# Analog_Supply_and_TIA.net
KiCad netlist of a schematic drawn in Altium Designer
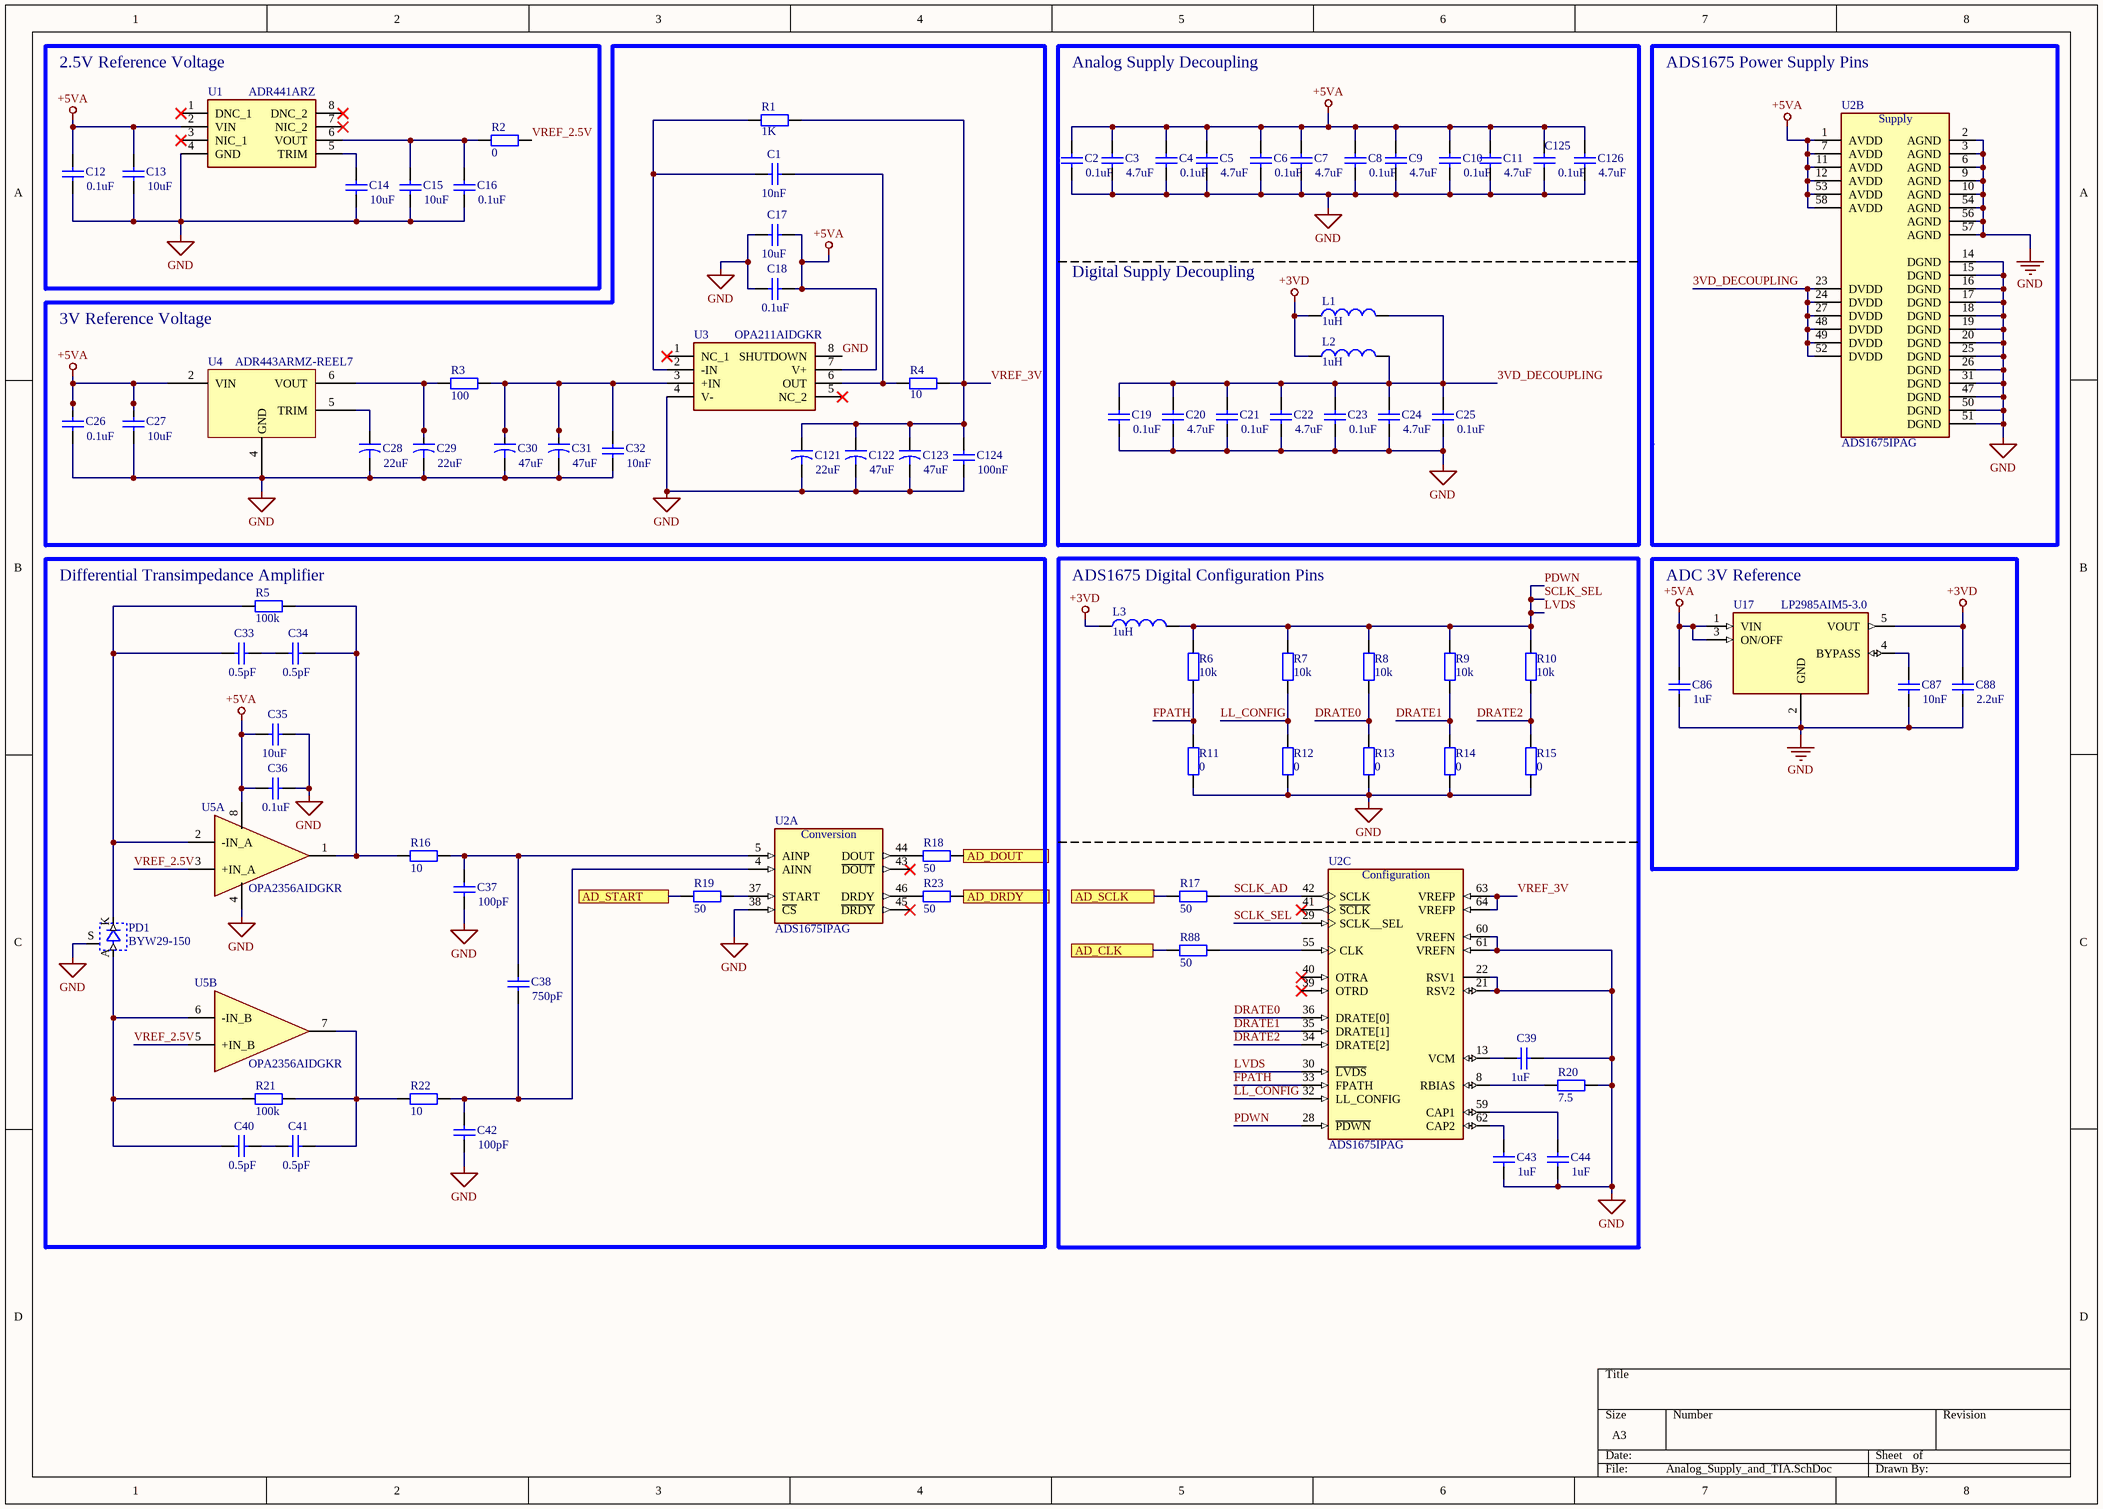
[diagram p0: Analog_Supply_and_TIA.SchDoc]

(export (version "E")
  (design (tool "Eeschema 10.0.6"))
  (components
    (comp (ref "C1")
      (value "10nF")
      (footprint "CC_0805")
      (description "Capacitor")
      (fields (field (name "Comment") "Cap") (field (name "PUBLISHER") "Altium Limited"))
      (libsource (lib "Miscellaneous Devices") (part "Cap"))
    )
    (comp (ref "C2")
      (value "0.1uF")
      (footprint "CC_0805")
      (description "Capacitor")
      (fields (field (name "Comment") "Cap") (field (name "PUBLISHER") "Altium Limited"))
      (libsource (lib "Miscellaneous Devices") (part "Cap"))
    )
    (comp (ref "C3")
      (value "4.7uF")
      (footprint "CC_0805")
      (description "Capacitor")
      (fields (field (name "Comment") "Cap") (field (name "PUBLISHER") "Altium Limited"))
      (libsource (lib "Miscellaneous Devices") (part "Cap"))
    )
    (comp (ref "C4")
      (value "0.1uF")
      (footprint "CC_0805")
      (description "Capacitor")
      (fields (field (name "Comment") "Cap") (field (name "PUBLISHER") "Altium Limited"))
      (libsource (lib "Miscellaneous Devices") (part "Cap"))
    )
    (comp (ref "C5")
      (value "4.7uF")
      (footprint "CC_0805")
      (description "Capacitor")
      (fields (field (name "Comment") "Cap") (field (name "PUBLISHER") "Altium Limited"))
      (libsource (lib "Miscellaneous Devices") (part "Cap"))
    )
    (comp (ref "C6")
      (value "0.1uF")
      (footprint "CC_0805")
      (description "Capacitor")
      (fields (field (name "Comment") "Cap") (field (name "PUBLISHER") "Altium Limited"))
      (libsource (lib "Miscellaneous Devices") (part "Cap"))
    )
    (comp (ref "C7")
      (value "4.7uF")
      (footprint "CC_0805")
      (description "Capacitor")
      (fields (field (name "Comment") "Cap") (field (name "PUBLISHER") "Altium Limited"))
      (libsource (lib "Miscellaneous Devices") (part "Cap"))
    )
    (comp (ref "C8")
      (value "0.1uF")
      (footprint "CC_0805")
      (description "Capacitor")
      (fields (field (name "Comment") "Cap") (field (name "PUBLISHER") "Altium Limited"))
      (libsource (lib "Miscellaneous Devices") (part "Cap"))
    )
    (comp (ref "C9")
      (value "4.7uF")
      (footprint "CC_0805")
      (description "Capacitor")
      (fields (field (name "Comment") "Cap") (field (name "PUBLISHER") "Altium Limited"))
      (libsource (lib "Miscellaneous Devices") (part "Cap"))
    )
    (comp (ref "C10")
      (value "0.1uF")
      (footprint "CC_0805")
      (description "Capacitor")
      (fields (field (name "Comment") "Cap") (field (name "PUBLISHER") "Altium Limited"))
      (libsource (lib "Miscellaneous Devices") (part "Cap"))
    )
    (comp (ref "C11")
      (value "4.7uF")
      (footprint "CC_0805")
      (description "Capacitor")
      (fields (field (name "Comment") "Cap") (field (name "PUBLISHER") "Altium Limited"))
      (libsource (lib "Miscellaneous Devices") (part "Cap"))
    )
    (comp (ref "C12")
      (value "0.1uF")
      (footprint "CC_0805")
      (description "Capacitor")
      (fields (field (name "Comment") "Cap") (field (name "PUBLISHER") "Altium Limited"))
      (libsource (lib "Miscellaneous Devices") (part "Cap"))
    )
    (comp (ref "C13")
      (value "10uF")
      (footprint "CC_0805")
      (description "Capacitor")
      (fields (field (name "Comment") "Cap") (field (name "PUBLISHER") "Altium Limited"))
      (libsource (lib "Miscellaneous Devices") (part "Cap"))
    )
    (comp (ref "C14")
      (value "10uF")
      (footprint "CC_0805")
      (description "Capacitor")
      (fields (field (name "Comment") "Cap") (field (name "PUBLISHER") "Altium Limited"))
      (libsource (lib "Miscellaneous Devices") (part "Cap"))
    )
    (comp (ref "C15")
      (value "10uF")
      (footprint "CC_0805")
      (description "Capacitor")
      (fields (field (name "Comment") "Cap") (field (name "PUBLISHER") "Altium Limited"))
      (libsource (lib "Miscellaneous Devices") (part "Cap"))
    )
    (comp (ref "C16")
      (value "0.1uF")
      (footprint "CC_0805")
      (description "Capacitor")
      (fields (field (name "Comment") "Cap") (field (name "PUBLISHER") "Altium Limited"))
      (libsource (lib "Miscellaneous Devices") (part "Cap"))
    )
    (comp (ref "C17")
      (value "10uF")
      (footprint "CC_0805")
      (description "Capacitor")
      (fields (field (name "Comment") "Cap") (field (name "PUBLISHER") "Altium Limited"))
      (libsource (lib "Miscellaneous Devices") (part "Cap"))
    )
    (comp (ref "C18")
      (value "0.1uF")
      (footprint "CC_0805")
      (description "Capacitor")
      (fields (field (name "Comment") "Cap") (field (name "PUBLISHER") "Altium Limited"))
      (libsource (lib "Miscellaneous Devices") (part "Cap"))
    )
    (comp (ref "C19")
      (value "0.1uF")
      (footprint "CC_0805")
      (description "Capacitor")
      (fields (field (name "Comment") "Cap") (field (name "PUBLISHER") "Altium Limited"))
      (libsource (lib "Miscellaneous Devices") (part "Cap"))
    )
    (comp (ref "C20")
      (value "4.7uF")
      (footprint "CC_0805")
      (description "Capacitor")
      (fields (field (name "Comment") "Cap") (field (name "PUBLISHER") "Altium Limited"))
      (libsource (lib "Miscellaneous Devices") (part "Cap"))
    )
    (comp (ref "C21")
      (value "0.1uF")
      (footprint "CC_0805")
      (description "Capacitor")
      (fields (field (name "Comment") "Cap") (field (name "PUBLISHER") "Altium Limited"))
      (libsource (lib "Miscellaneous Devices") (part "Cap"))
    )
    (comp (ref "C22")
      (value "4.7uF")
      (footprint "CC_0805")
      (description "Capacitor")
      (fields (field (name "Comment") "Cap") (field (name "PUBLISHER") "Altium Limited"))
      (libsource (lib "Miscellaneous Devices") (part "Cap"))
    )
    (comp (ref "C23")
      (value "0.1uF")
      (footprint "CC_0805")
      (description "Capacitor")
      (fields (field (name "Comment") "Cap") (field (name "PUBLISHER") "Altium Limited"))
      (libsource (lib "Miscellaneous Devices") (part "Cap"))
    )
    (comp (ref "C24")
      (value "4.7uF")
      (footprint "CC_0805")
      (description "Capacitor")
      (fields (field (name "Comment") "Cap") (field (name "PUBLISHER") "Altium Limited"))
      (libsource (lib "Miscellaneous Devices") (part "Cap"))
    )
    (comp (ref "C25")
      (value "0.1uF")
      (footprint "CC_0805")
      (description "Capacitor")
      (fields (field (name "Comment") "Cap") (field (name "PUBLISHER") "Altium Limited"))
      (libsource (lib "Miscellaneous Devices") (part "Cap"))
    )
    (comp (ref "C26")
      (value "0.1uF")
      (footprint "CC_0805")
      (description "Capacitor")
      (fields (field (name "Comment") "Cap") (field (name "PUBLISHER") "Altium Limited"))
      (libsource (lib "Miscellaneous Devices") (part "Cap"))
    )
    (comp (ref "C27")
      (value "10uF")
      (footprint "CC_0805")
      (description "Capacitor")
      (fields (field (name "Comment") "Cap") (field (name "PUBLISHER") "Altium Limited"))
      (libsource (lib "Miscellaneous Devices") (part "Cap"))
    )
    (comp (ref "C28")
      (value "22uF")
      (footprint "CC_0805")
      (description "Capacitor")
      (fields (field (name "Comment") "Cap2") (field (name "PUBLISHER") "Altium Limited"))
      (libsource (lib "Miscellaneous Devices") (part "Cap2"))
    )
    (comp (ref "C29")
      (value "22uF")
      (footprint "CC_0805")
      (description "Capacitor")
      (fields (field (name "Comment") "Cap2") (field (name "PUBLISHER") "Altium Limited"))
      (libsource (lib "Miscellaneous Devices") (part "Cap2"))
    )
    (comp (ref "C30")
      (value "47uF")
      (footprint "CC_0805")
      (description "Capacitor")
      (fields (field (name "Comment") "Cap2") (field (name "PUBLISHER") "Altium Limited"))
      (libsource (lib "Miscellaneous Devices") (part "Cap2"))
    )
    (comp (ref "C31")
      (value "47uF")
      (footprint "CC_0805")
      (description "Capacitor")
      (fields (field (name "Comment") "Cap2") (field (name "PUBLISHER") "Altium Limited"))
      (libsource (lib "Miscellaneous Devices") (part "Cap2"))
    )
    (comp (ref "C32")
      (value "10nF")
      (footprint "CC_0805")
      (description "Capacitor")
      (fields (field (name "Comment") "Cap") (field (name "PUBLISHER") "Altium Limited"))
      (libsource (lib "Miscellaneous Devices") (part "Cap"))
    )
    (comp (ref "C33")
      (value "0.5pF")
      (footprint "CC_0805")
      (description "Capacitor")
      (fields (field (name "Comment") "Cap") (field (name "PUBLISHER") "Altium Limited"))
      (libsource (lib "Miscellaneous Devices") (part "Cap"))
    )
    (comp (ref "C34")
      (value "0.5pF")
      (footprint "CC_0805")
      (description "Capacitor")
      (fields (field (name "Comment") "Cap") (field (name "PUBLISHER") "Altium Limited"))
      (libsource (lib "Miscellaneous Devices") (part "Cap"))
    )
    (comp (ref "C35")
      (value "10uF")
      (footprint "CC_0805")
      (description "Capacitor")
      (fields (field (name "Comment") "Cap") (field (name "PUBLISHER") "Altium Limited"))
      (libsource (lib "Miscellaneous Devices") (part "Cap"))
    )
    (comp (ref "C36")
      (value "0.1uF")
      (footprint "CC_0805")
      (description "Capacitor")
      (fields (field (name "Comment") "Cap") (field (name "PUBLISHER") "Altium Limited"))
      (libsource (lib "Miscellaneous Devices") (part "Cap"))
    )
    (comp (ref "C37")
      (value "100pF")
      (footprint "CC_0805")
      (description "Capacitor")
      (fields (field (name "Comment") "Cap") (field (name "PUBLISHER") "Altium Limited"))
      (libsource (lib "Miscellaneous Devices") (part "Cap"))
    )
    (comp (ref "C38")
      (value "750pF")
      (footprint "CC_0805")
      (description "Capacitor")
      (fields (field (name "Comment") "Cap") (field (name "PUBLISHER") "Altium Limited"))
      (libsource (lib "Miscellaneous Devices") (part "Cap"))
    )
    (comp (ref "C39")
      (value "1uF")
      (footprint "CC_0805")
      (description "Capacitor")
      (fields (field (name "Comment") "Cap") (field (name "PUBLISHER") "Altium Limited"))
      (libsource (lib "Miscellaneous Devices") (part "Cap"))
    )
    (comp (ref "C40")
      (value "0.5pF")
      (footprint "CC_0805")
      (description "Capacitor")
      (fields (field (name "Comment") "Cap") (field (name "PUBLISHER") "Altium Limited"))
      (libsource (lib "Miscellaneous Devices") (part "Cap"))
    )
    (comp (ref "C41")
      (value "0.5pF")
      (footprint "CC_0805")
      (description "Capacitor")
      (fields (field (name "Comment") "Cap") (field (name "PUBLISHER") "Altium Limited"))
      (libsource (lib "Miscellaneous Devices") (part "Cap"))
    )
    (comp (ref "C42")
      (value "100pF")
      (footprint "CC_0805")
      (description "Capacitor")
      (fields (field (name "Comment") "Cap") (field (name "PUBLISHER") "Altium Limited"))
      (libsource (lib "Miscellaneous Devices") (part "Cap"))
    )
    (comp (ref "C43")
      (value "1uF")
      (footprint "CC_0805")
      (description "Capacitor")
      (fields (field (name "Comment") "Cap") (field (name "PUBLISHER") "Altium Limited"))
      (libsource (lib "Miscellaneous Devices") (part "Cap"))
    )
    (comp (ref "C44")
      (value "1uF")
      (footprint "CC_0805")
      (description "Capacitor")
      (fields (field (name "Comment") "Cap") (field (name "PUBLISHER") "Altium Limited"))
      (libsource (lib "Miscellaneous Devices") (part "Cap"))
    )
    (comp (ref "C86")
      (value "1uF")
      (footprint "CC_0805")
      (description "Capacitor")
      (fields (field (name "Comment") "Cap") (field (name "PUBLISHER") "Altium Limited"))
      (libsource (lib "Miscellaneous Devices") (part "Cap"))
    )
    (comp (ref "C87")
      (value "10nF")
      (footprint "CC_0805")
      (description "Capacitor")
      (fields (field (name "Comment") "Cap") (field (name "PUBLISHER") "Altium Limited"))
      (libsource (lib "Miscellaneous Devices") (part "Cap"))
    )
    (comp (ref "C88")
      (value "2.2uF")
      (footprint "CC_0805")
      (description "Capacitor")
      (fields (field (name "Comment") "Cap") (field (name "PUBLISHER") "Altium Limited"))
      (libsource (lib "Miscellaneous Devices") (part "Cap"))
    )
    (comp (ref "C121")
      (value "22uF")
      (footprint "CC_0805")
      (description "Capacitor")
      (fields (field (name "Comment") "Cap2") (field (name "PUBLISHER") "Altium Limited"))
      (libsource (lib "Miscellaneous Devices") (part "Cap2"))
    )
    (comp (ref "C122")
      (value "47uF")
      (footprint "CC_0805")
      (description "Capacitor")
      (fields (field (name "Comment") "Cap2") (field (name "PUBLISHER") "Altium Limited"))
      (libsource (lib "Miscellaneous Devices") (part "Cap2"))
    )
    (comp (ref "C123")
      (value "47uF")
      (footprint "CC_0805")
      (description "Capacitor")
      (fields (field (name "Comment") "Cap2") (field (name "PUBLISHER") "Altium Limited"))
      (libsource (lib "Miscellaneous Devices") (part "Cap2"))
    )
    (comp (ref "C124")
      (value "100nF")
      (footprint "CC_0805")
      (description "Capacitor")
      (fields (field (name "Comment") "Cap") (field (name "PUBLISHER") "Altium Limited"))
      (libsource (lib "Miscellaneous Devices") (part "Cap"))
    )
    (comp (ref "C125")
      (value "0.1uF")
      (footprint "CC_0805")
      (description "Capacitor")
      (fields (field (name "Comment") "Cap") (field (name "PUBLISHER") "Altium Limited"))
      (libsource (lib "Miscellaneous Devices") (part "Cap"))
    )
    (comp (ref "C126")
      (value "4.7uF")
      (footprint "CC_0805")
      (description "Capacitor")
      (fields (field (name "Comment") "Cap") (field (name "PUBLISHER") "Altium Limited"))
      (libsource (lib "Miscellaneous Devices") (part "Cap"))
    )
    (comp (ref "L1")
      (value "1uH")
      (footprint "WE-PMI_0805_H0.5")
      (description "Inductor")
      (fields (field (name "PUBLISHER") "Altium Limited"))
      (libsource (lib "Miscellaneous Devices") (part "Inductor"))
    )
    (comp (ref "L2")
      (value "1uH")
      (footprint "WE-PMI_0805_H0.5")
      (description "Inductor")
      (fields (field (name "PUBLISHER") "Altium Limited"))
      (libsource (lib "Miscellaneous Devices") (part "Inductor"))
    )
    (comp (ref "L3")
      (value "1uH")
      (footprint "WE-PMI_0805_H0.5")
      (description "Inductor")
      (fields (field (name "PUBLISHER") "Altium Limited"))
      (libsource (lib "Miscellaneous Devices") (part "Inductor"))
    )
    (comp (ref "PD1")
      (value "BYW29-150")
      (footprint "BYW29-150")
      (libsource (lib "Lib_Schematic_IFOG_Interrogator") (part "BYW29-150"))
    )
    (comp (ref "R1")
      (value "1K")
      (footprint "RR_1220")
      (description "Resistor")
      (fields (field (name "Comment") "Res2") (field (name "PUBLISHER") "Altium Limited"))
      (libsource (lib "") (part "Res2_1"))
    )
    (comp (ref "R2")
      (value "0")
      (footprint "RR_1220")
      (description "Resistor")
      (fields (field (name "Comment") "Res2") (field (name "PUBLISHER") "Altium Limited"))
      (libsource (lib "") (part "Res2_2"))
    )
    (comp (ref "R3")
      (value "100")
      (footprint "RR_1220")
      (description "Resistor")
      (fields (field (name "Comment") "Res2") (field (name "PUBLISHER") "Altium Limited"))
      (libsource (lib "") (part "Res2_2"))
    )
    (comp (ref "R4")
      (value "10")
      (footprint "RR_1220")
      (description "Resistor")
      (fields (field (name "Comment") "Res2") (field (name "PUBLISHER") "Altium Limited"))
      (libsource (lib "") (part "Res2_1"))
    )
    (comp (ref "R5")
      (value "100k")
      (footprint "RR_1220")
      (description "Resistor")
      (fields (field (name "Comment") "Res2") (field (name "PUBLISHER") "Altium Limited"))
      (libsource (lib "") (part "Res2_2"))
    )
    (comp (ref "R6")
      (value "10k")
      (footprint "RR_1220")
      (description "Resistor")
      (fields (field (name "Comment") "Res2") (field (name "PUBLISHER") "Altium Limited"))
      (libsource (lib "Miscellaneous Devices") (part "Res2"))
    )
    (comp (ref "R7")
      (value "10k")
      (footprint "RR_1220")
      (description "Resistor")
      (fields (field (name "Comment") "Res2") (field (name "PUBLISHER") "Altium Limited"))
      (libsource (lib "Miscellaneous Devices") (part "Res2"))
    )
    (comp (ref "R8")
      (value "10k")
      (footprint "RR_1220")
      (description "Resistor")
      (fields (field (name "Comment") "Res2") (field (name "PUBLISHER") "Altium Limited"))
      (libsource (lib "Miscellaneous Devices") (part "Res2"))
    )
    (comp (ref "R9")
      (value "10k")
      (footprint "RR_1220")
      (description "Resistor")
      (fields (field (name "Comment") "Res2") (field (name "PUBLISHER") "Altium Limited"))
      (libsource (lib "Miscellaneous Devices") (part "Res2"))
    )
    (comp (ref "R10")
      (value "10k")
      (footprint "RR_1220")
      (description "Resistor")
      (fields (field (name "Comment") "Res2") (field (name "PUBLISHER") "Altium Limited"))
      (libsource (lib "Miscellaneous Devices") (part "Res2"))
    )
    (comp (ref "R11")
      (value "0")
      (footprint "RR_1220")
      (description "Resistor")
      (fields (field (name "Comment") "Res2") (field (name "PUBLISHER") "Altium Limited"))
      (libsource (lib "Miscellaneous Devices") (part "Res2"))
    )
    (comp (ref "R12")
      (value "0")
      (footprint "RR_1220")
      (description "Resistor")
      (fields (field (name "Comment") "Res2") (field (name "PUBLISHER") "Altium Limited"))
      (libsource (lib "Miscellaneous Devices") (part "Res2"))
    )
    (comp (ref "R13")
      (value "0")
      (footprint "RR_1220")
      (description "Resistor")
      (fields (field (name "Comment") "Res2") (field (name "PUBLISHER") "Altium Limited"))
      (libsource (lib "Miscellaneous Devices") (part "Res2"))
    )
    (comp (ref "R14")
      (value "0")
      (footprint "RR_1220")
      (description "Resistor")
      (fields (field (name "Comment") "Res2") (field (name "PUBLISHER") "Altium Limited"))
      (libsource (lib "Miscellaneous Devices") (part "Res2"))
    )
    (comp (ref "R15")
      (value "0")
      (footprint "RR_1220")
      (description "Resistor")
      (fields (field (name "Comment") "Res2") (field (name "PUBLISHER") "Altium Limited"))
      (libsource (lib "Miscellaneous Devices") (part "Res2"))
    )
    (comp (ref "R16")
      (value "10")
      (footprint "RR_1220")
      (description "Resistor")
      (fields (field (name "Comment") "Res2") (field (name "PUBLISHER") "Altium Limited"))
      (libsource (lib "") (part "Res2_2"))
    )
    (comp (ref "R17")
      (value "50")
      (footprint "RR_1220")
      (description "Resistor")
      (fields (field (name "Comment") "Res2") (field (name "PUBLISHER") "Altium Limited"))
      (libsource (lib "") (part "Res2_2"))
    )
    (comp (ref "R18")
      (value "50")
      (footprint "RR_1220")
      (description "Resistor")
      (fields (field (name "Comment") "Res2") (field (name "PUBLISHER") "Altium Limited"))
      (libsource (lib "") (part "Res2_2"))
    )
    (comp (ref "R19")
      (value "50")
      (footprint "RR_1220")
      (description "Resistor")
      (fields (field (name "Comment") "Res2") (field (name "PUBLISHER") "Altium Limited"))
      (libsource (lib "") (part "Res2_2"))
    )
    (comp (ref "R20")
      (value "7.5")
      (footprint "RR_1220")
      (description "Resistor")
      (fields (field (name "Comment") "Res2") (field (name "PUBLISHER") "Altium Limited"))
      (libsource (lib "") (part "Res2_2"))
    )
    (comp (ref "R21")
      (value "100k")
      (footprint "RR_1220")
      (description "Resistor")
      (fields (field (name "Comment") "Res2") (field (name "PUBLISHER") "Altium Limited"))
      (libsource (lib "") (part "Res2_2"))
    )
    (comp (ref "R22")
      (value "10")
      (footprint "RR_1220")
      (description "Resistor")
      (fields (field (name "Comment") "Res2") (field (name "PUBLISHER") "Altium Limited"))
      (libsource (lib "") (part "Res2_2"))
    )
    (comp (ref "R23")
      (value "50")
      (footprint "RR_1220")
      (description "Resistor")
      (fields (field (name "Comment") "Res2") (field (name "PUBLISHER") "Altium Limited"))
      (libsource (lib "") (part "Res2_2"))
    )
    (comp (ref "R88")
      (value "50")
      (footprint "RR_1220")
      (description "Resistor")
      (fields (field (name "Comment") "Res2") (field (name "PUBLISHER") "Altium Limited"))
      (libsource (lib "") (part "Res2_2"))
    )
    (comp (ref "U1")
      (value "ADR441ARZ")
      (footprint "ADR441ARZ")
      (description "Series Voltage Reference IC Fixed 2.5V V +/-0.12% 10 mA 8-SOIC")
      (fields (field (name "MOUSER PART NUMBER") "584-ADR441ARZ"))
      (libsource (lib "Lib_Schematic_Gyro_Single_Axis") (part "ADR441ARZ"))
    )
    (comp (ref "U2")
      (value "ADS1675IPAG")
      (footprint "ADS1675IPAG")
      (description "4MSPS, 24-Bit Analog-to-Digital Converter")
      (fields (field (name "MF") "Texas Instruments"))
      (libsource (lib "Lib_Schematic_IFOG_Interrogator") (part "ADS1675IPAG"))
    )
    (comp (ref "U3")
      (value "OPA211AIDGKR")
      (footprint "OPA211AIDGKR")
      (description "Precision Amplifiers 1.1nV/rtHz Noise Lo Pwr Prec Op Amp")
      (fields (field (name "MOUSER PART NUMBER") "595-OPA211AIDGKR"))
      (libsource (lib "Lib_Schematic_Gyro_Single_Axis") (part "OPA211AIDGKR"))
    )
    (comp (ref "U4")
      (value "ADR443ARMZ-REEL7")
      (footprint "ADR443ARMZ-REEL7 - duplicate")
      (libsource (lib "Lib_Schematic_Gyro_Single_Axis") (part "ADR443ARMZ-REEL7"))
    )
    (comp (ref "U5")
      (value "OPA2356AIDGKR")
      (footprint "OPA2356AIDGKR")
      (description "High Speed Operational Amplifiers 2.5V 200MHz GBW CMOS Dual Op Amp")
      (fields (field (name "MOUSER PART NUMBER") "595-OPA2356AIDGKR"))
      (libsource (lib "Lib_Schematic_Gyro_Single_Axis") (part "OPA2356AIDGKR"))
    )
    (comp (ref "U17")
      (value "LP2985AIM5-3.0")
      (footprint "LP2985AIM5-3.0")
      (description "150-mA, 16-V, low-dropout voltage regulator with enable")
      (fields (field (name "MF") "Texas Instruments") (field (name "MP") "LP2985AIM5-3.0/NOPB"))
      (libsource (lib "Lib_Schematic_Gyro_Single_Axis") (part "LP2985AIM5-3.0"))
    )
  )
  (nets
    (net (code "1") (name "+3VD") (class "Default")
      (node (ref "C88") (pin "1") (pinfunction "1_1") (pintype "passive"))
      (node (ref "L1") (pin "1") (pinfunction "1_1") (pintype "passive"))
      (node (ref "L2") (pin "1") (pinfunction "1_1") (pintype "passive"))
      (node (ref "L3") (pin "1") (pinfunction "1_1") (pintype "passive"))
      (node (ref "U17") (pin "5") (pinfunction "VOUT_5") (pintype "output"))
    )
    (net (code "2") (name "+5VA") (class "Default")
      (node (ref "C10") (pin "2") (pinfunction "2_2") (pintype "passive"))
      (node (ref "C11") (pin "2") (pinfunction "2_2") (pintype "passive"))
      (node (ref "C12") (pin "2") (pinfunction "2_2") (pintype "passive"))
      (node (ref "C125") (pin "2") (pinfunction "2_2") (pintype "passive"))
      (node (ref "C126") (pin "2") (pinfunction "2_2") (pintype "passive"))
      (node (ref "C13") (pin "2") (pinfunction "2_2") (pintype "passive"))
      (node (ref "C17") (pin "1") (pinfunction "1_1") (pintype "passive"))
      (node (ref "C18") (pin "1") (pinfunction "1_1") (pintype "passive"))
      (node (ref "C2") (pin "2") (pinfunction "2_2") (pintype "passive"))
      (node (ref "C26") (pin "2") (pinfunction "2_2") (pintype "passive"))
      (node (ref "C27") (pin "2") (pinfunction "2_2") (pintype "passive"))
      (node (ref "C3") (pin "2") (pinfunction "2_2") (pintype "passive"))
      (node (ref "C35") (pin "2") (pinfunction "2_2") (pintype "passive"))
      (node (ref "C36") (pin "2") (pinfunction "2_2") (pintype "passive"))
      (node (ref "C4") (pin "2") (pinfunction "2_2") (pintype "passive"))
      (node (ref "C5") (pin "2") (pinfunction "2_2") (pintype "passive"))
      (node (ref "C6") (pin "2") (pinfunction "2_2") (pintype "passive"))
      (node (ref "C7") (pin "2") (pinfunction "2_2") (pintype "passive"))
      (node (ref "C8") (pin "2") (pinfunction "2_2") (pintype "passive"))
      (node (ref "C86") (pin "1") (pinfunction "1_1") (pintype "passive"))
      (node (ref "C9") (pin "2") (pinfunction "2_2") (pintype "passive"))
      (node (ref "U1") (pin "2") (pinfunction "VIN_2") (pintype "passive"))
      (node (ref "U17") (pin "1") (pinfunction "VIN_1") (pintype "input"))
      (node (ref "U17") (pin "3") (pinfunction "ON/OFF_3") (pintype "input"))
      (node (ref "U2") (pin "1") (pinfunction "AVDD_1") (pintype "power_in"))
      (node (ref "U2") (pin "11") (pinfunction "AVDD_11") (pintype "power_in"))
      (node (ref "U2") (pin "12") (pinfunction "AVDD_12") (pintype "power_in"))
      (node (ref "U2") (pin "53") (pinfunction "AVDD_53") (pintype "power_in"))
      (node (ref "U2") (pin "58") (pinfunction "AVDD_58") (pintype "power_in"))
      (node (ref "U2") (pin "7") (pinfunction "AVDD_7") (pintype "power_in"))
      (node (ref "U3") (pin "7") (pinfunction "V+_7") (pintype "passive"))
      (node (ref "U4") (pin "2") (pinfunction "VIN_2") (pintype "passive"))
      (node (ref "U5") (pin "8") (pinfunction "V+_8") (pintype "passive"))
    )
    (net (code "3") (name "/3VD_DECOUPLING") (class "Default")
      (node (ref "C19") (pin "2") (pinfunction "2_2") (pintype "passive"))
      (node (ref "C20") (pin "2") (pinfunction "2_2") (pintype "passive"))
      (node (ref "C21") (pin "2") (pinfunction "2_2") (pintype "passive"))
      (node (ref "C22") (pin "2") (pinfunction "2_2") (pintype "passive"))
      (node (ref "C23") (pin "2") (pinfunction "2_2") (pintype "passive"))
      (node (ref "C24") (pin "2") (pinfunction "2_2") (pintype "passive"))
      (node (ref "C25") (pin "2") (pinfunction "2_2") (pintype "passive"))
      (node (ref "L1") (pin "2") (pinfunction "2_2") (pintype "passive"))
      (node (ref "L2") (pin "2") (pinfunction "2_2") (pintype "passive"))
      (node (ref "U2") (pin "23") (pinfunction "DVDD_23") (pintype "power_in"))
      (node (ref "U2") (pin "24") (pinfunction "DVDD_24") (pintype "power_in"))
      (node (ref "U2") (pin "27") (pinfunction "DVDD_27") (pintype "power_in"))
      (node (ref "U2") (pin "48") (pinfunction "DVDD_48") (pintype "power_in"))
      (node (ref "U2") (pin "49") (pinfunction "DVDD_49") (pintype "power_in"))
      (node (ref "U2") (pin "52") (pinfunction "DVDD_52") (pintype "power_in"))
    )
    (net (code "4") (name "/AD_CLK") (class "Default")
      (node (ref "R88") (pin "1") (pinfunction "1_1") (pintype "passive"))
    )
    (net (code "5") (name "/AD_DOUT") (class "Default")
      (node (ref "R18") (pin "2") (pinfunction "2_2") (pintype "passive"))
    )
    (net (code "6") (name "/AD_DRDY") (class "Default")
      (node (ref "R23") (pin "2") (pinfunction "2_2") (pintype "passive"))
    )
    (net (code "7") (name "/AD_SCLK") (class "Default")
      (node (ref "R17") (pin "1") (pinfunction "1_1") (pintype "passive"))
    )
    (net (code "8") (name "/AD_START") (class "Default")
      (node (ref "R19") (pin "1") (pinfunction "1_1") (pintype "passive"))
    )
    (net (code "9") (name "/DRATE0") (class "Default")
      (node (ref "R13") (pin "2") (pinfunction "2_2") (pintype "passive"))
      (node (ref "R8") (pin "1") (pinfunction "1_1") (pintype "passive"))
      (node (ref "U2") (pin "36") (pinfunction "DRATE[0]_36") (pintype "input"))
    )
    (net (code "10") (name "/DRATE1") (class "Default")
      (node (ref "R14") (pin "2") (pinfunction "2_2") (pintype "passive"))
      (node (ref "R9") (pin "1") (pinfunction "1_1") (pintype "passive"))
      (node (ref "U2") (pin "35") (pinfunction "DRATE[1]_35") (pintype "input"))
    )
    (net (code "11") (name "/DRATE2") (class "Default")
      (node (ref "R10") (pin "1") (pinfunction "1_1") (pintype "passive"))
      (node (ref "R15") (pin "2") (pinfunction "2_2") (pintype "passive"))
      (node (ref "U2") (pin "34") (pinfunction "DRATE[2]_34") (pintype "input"))
    )
    (net (code "12") (name "/FPATH") (class "Default")
      (node (ref "R11") (pin "2") (pinfunction "2_2") (pintype "passive"))
      (node (ref "R6") (pin "1") (pinfunction "1_1") (pintype "passive"))
      (node (ref "U2") (pin "33") (pinfunction "FPATH_33") (pintype "input"))
    )
    (net (code "13") (name "/LL_CONFIG") (class "Default")
      (node (ref "R12") (pin "2") (pinfunction "2_2") (pintype "passive"))
      (node (ref "R7") (pin "1") (pinfunction "1_1") (pintype "passive"))
      (node (ref "U2") (pin "32") (pinfunction "LL_CONFIG_32") (pintype "input"))
    )
    (net (code "14") (name "/LVDS") (class "Default")
      (node (ref "L3") (pin "2") (pinfunction "2_2") (pintype "passive"))
      (node (ref "R10") (pin "2") (pinfunction "2_2") (pintype "passive"))
      (node (ref "R6") (pin "2") (pinfunction "2_2") (pintype "passive"))
      (node (ref "R7") (pin "2") (pinfunction "2_2") (pintype "passive"))
      (node (ref "R8") (pin "2") (pinfunction "2_2") (pintype "passive"))
      (node (ref "R9") (pin "2") (pinfunction "2_2") (pintype "passive"))
      (node (ref "U2") (pin "28") (pinfunction "~{PDWN}_28") (pintype "input"))
      (node (ref "U2") (pin "29") (pinfunction "SCLK__SEL_29") (pintype "input"))
      (node (ref "U2") (pin "30") (pinfunction "~{LVDS}_30") (pintype "input"))
    )
    (net (code "15") (name "/SCLK_AD") (class "Default")
      (node (ref "R17") (pin "2") (pinfunction "2_2") (pintype "passive"))
      (node (ref "U2") (pin "42") (pinfunction "SCLK_42") (pintype "output"))
    )
    (net (code "16") (name "/VREF_2.5V") (class "Default")
      (node (ref "R2") (pin "2") (pinfunction "2_2") (pintype "passive"))
      (node (ref "U5") (pin "3") (pinfunction "+IN_A_3") (pintype "passive"))
      (node (ref "U5") (pin "5") (pinfunction "+IN_B_5") (pintype "passive"))
    )
    (net (code "17") (name "/VREF_3V") (class "Default")
      (node (ref "C121") (pin "1") (pinfunction "1_1") (pintype "passive"))
      (node (ref "C122") (pin "1") (pinfunction "1_1") (pintype "passive"))
      (node (ref "C123") (pin "1") (pinfunction "1_1") (pintype "passive"))
      (node (ref "C124") (pin "2") (pinfunction "2_2") (pintype "passive"))
      (node (ref "R1") (pin "1") (pinfunction "1_1") (pintype "passive"))
      (node (ref "R4") (pin "1") (pinfunction "1_1") (pintype "passive"))
      (node (ref "U2") (pin "63") (pinfunction "VREFP_63") (pintype "input"))
      (node (ref "U2") (pin "64") (pinfunction "VREFP_64") (pintype "input"))
    )
    (net (code "18") (name "GND") (class "Default")
      (node (ref "C10") (pin "1") (pinfunction "1_1") (pintype "passive"))
      (node (ref "C11") (pin "1") (pinfunction "1_1") (pintype "passive"))
      (node (ref "C12") (pin "1") (pinfunction "1_1") (pintype "passive"))
      (node (ref "C121") (pin "2") (pinfunction "2_2") (pintype "passive"))
      (node (ref "C122") (pin "2") (pinfunction "2_2") (pintype "passive"))
      (node (ref "C123") (pin "2") (pinfunction "2_2") (pintype "passive"))
      (node (ref "C124") (pin "1") (pinfunction "1_1") (pintype "passive"))
      (node (ref "C125") (pin "1") (pinfunction "1_1") (pintype "passive"))
      (node (ref "C126") (pin "1") (pinfunction "1_1") (pintype "passive"))
      (node (ref "C13") (pin "1") (pinfunction "1_1") (pintype "passive"))
      (node (ref "C14") (pin "1") (pinfunction "1_1") (pintype "passive"))
      (node (ref "C15") (pin "1") (pinfunction "1_1") (pintype "passive"))
      (node (ref "C16") (pin "1") (pinfunction "1_1") (pintype "passive"))
      (node (ref "C17") (pin "2") (pinfunction "2_2") (pintype "passive"))
      (node (ref "C18") (pin "2") (pinfunction "2_2") (pintype "passive"))
      (node (ref "C19") (pin "1") (pinfunction "1_1") (pintype "passive"))
      (node (ref "C2") (pin "1") (pinfunction "1_1") (pintype "passive"))
      (node (ref "C20") (pin "1") (pinfunction "1_1") (pintype "passive"))
      (node (ref "C21") (pin "1") (pinfunction "1_1") (pintype "passive"))
      (node (ref "C22") (pin "1") (pinfunction "1_1") (pintype "passive"))
      (node (ref "C23") (pin "1") (pinfunction "1_1") (pintype "passive"))
      (node (ref "C24") (pin "1") (pinfunction "1_1") (pintype "passive"))
      (node (ref "C25") (pin "1") (pinfunction "1_1") (pintype "passive"))
      (node (ref "C26") (pin "1") (pinfunction "1_1") (pintype "passive"))
      (node (ref "C27") (pin "1") (pinfunction "1_1") (pintype "passive"))
      (node (ref "C28") (pin "2") (pinfunction "2_2") (pintype "passive"))
      (node (ref "C29") (pin "2") (pinfunction "2_2") (pintype "passive"))
      (node (ref "C3") (pin "1") (pinfunction "1_1") (pintype "passive"))
      (node (ref "C30") (pin "2") (pinfunction "2_2") (pintype "passive"))
      (node (ref "C31") (pin "2") (pinfunction "2_2") (pintype "passive"))
      (node (ref "C32") (pin "1") (pinfunction "1_1") (pintype "passive"))
      (node (ref "C35") (pin "1") (pinfunction "1_1") (pintype "passive"))
      (node (ref "C36") (pin "1") (pinfunction "1_1") (pintype "passive"))
      (node (ref "C37") (pin "1") (pinfunction "1_1") (pintype "passive"))
      (node (ref "C39") (pin "1") (pinfunction "1_1") (pintype "passive"))
      (node (ref "C4") (pin "1") (pinfunction "1_1") (pintype "passive"))
      (node (ref "C42") (pin "1") (pinfunction "1_1") (pintype "passive"))
      (node (ref "C43") (pin "2") (pinfunction "2_2") (pintype "passive"))
      (node (ref "C44") (pin "2") (pinfunction "2_2") (pintype "passive"))
      (node (ref "C5") (pin "1") (pinfunction "1_1") (pintype "passive"))
      (node (ref "C6") (pin "1") (pinfunction "1_1") (pintype "passive"))
      (node (ref "C7") (pin "1") (pinfunction "1_1") (pintype "passive"))
      (node (ref "C8") (pin "1") (pinfunction "1_1") (pintype "passive"))
      (node (ref "C86") (pin "2") (pinfunction "2_2") (pintype "passive"))
      (node (ref "C87") (pin "2") (pinfunction "2_2") (pintype "passive"))
      (node (ref "C88") (pin "2") (pinfunction "2_2") (pintype "passive"))
      (node (ref "C9") (pin "1") (pinfunction "1_1") (pintype "passive"))
      (node (ref "PD1") (pin "S") (pinfunction "S_S") (pintype "passive"))
      (node (ref "R11") (pin "1") (pinfunction "1_1") (pintype "passive"))
      (node (ref "R12") (pin "1") (pinfunction "1_1") (pintype "passive"))
      (node (ref "R13") (pin "1") (pinfunction "1_1") (pintype "passive"))
      (node (ref "R14") (pin "1") (pinfunction "1_1") (pintype "passive"))
      (node (ref "R15") (pin "1") (pinfunction "1_1") (pintype "passive"))
      (node (ref "R20") (pin "2") (pinfunction "2_2") (pintype "passive"))
      (node (ref "U1") (pin "4") (pinfunction "GND_4") (pintype "passive"))
      (node (ref "U17") (pin "2") (pinfunction "GND_2") (pintype "power_in"))
      (node (ref "U2") (pin "10") (pinfunction "AGND_10") (pintype "power_in"))
      (node (ref "U2") (pin "14") (pinfunction "DGND_14") (pintype "power_in"))
      (node (ref "U2") (pin "15") (pinfunction "DGND_15") (pintype "power_in"))
      (node (ref "U2") (pin "16") (pinfunction "DGND_16") (pintype "power_in"))
      (node (ref "U2") (pin "17") (pinfunction "DGND_17") (pintype "power_in"))
      (node (ref "U2") (pin "18") (pinfunction "DGND_18") (pintype "power_in"))
      (node (ref "U2") (pin "19") (pinfunction "DGND_19") (pintype "power_in"))
      (node (ref "U2") (pin "2") (pinfunction "AGND_2") (pintype "power_in"))
      (node (ref "U2") (pin "20") (pinfunction "DGND_20") (pintype "power_in"))
      (node (ref "U2") (pin "21") (pinfunction "RSV2_21") (pintype "bidirectional"))
      (node (ref "U2") (pin "22") (pinfunction "RSV1_22") (pintype "power_in"))
      (node (ref "U2") (pin "25") (pinfunction "DGND_25") (pintype "power_in"))
      (node (ref "U2") (pin "26") (pinfunction "DGND_26") (pintype "power_in"))
      (node (ref "U2") (pin "3") (pinfunction "AGND_3") (pintype "power_in"))
      (node (ref "U2") (pin "31") (pinfunction "DGND_31") (pintype "power_in"))
      (node (ref "U2") (pin "38") (pinfunction "~{CS}_38") (pintype "input"))
      (node (ref "U2") (pin "47") (pinfunction "DGND_47") (pintype "power_in"))
      (node (ref "U2") (pin "50") (pinfunction "DGND_50") (pintype "power_in"))
      (node (ref "U2") (pin "51") (pinfunction "DGND_51") (pintype "power_in"))
      (node (ref "U2") (pin "54") (pinfunction "AGND_54") (pintype "power_in"))
      (node (ref "U2") (pin "56") (pinfunction "AGND_56") (pintype "power_in"))
      (node (ref "U2") (pin "57") (pinfunction "AGND_57") (pintype "power_in"))
      (node (ref "U2") (pin "6") (pinfunction "AGND_6") (pintype "power_in"))
      (node (ref "U2") (pin "60") (pinfunction "VREFN_60") (pintype "input"))
      (node (ref "U2") (pin "61") (pinfunction "VREFN_61") (pintype "input"))
      (node (ref "U2") (pin "9") (pinfunction "AGND_9") (pintype "power_in"))
      (node (ref "U3") (pin "4") (pinfunction "V-_4") (pintype "passive"))
      (node (ref "U3") (pin "8") (pinfunction "SHUTDOWN_8") (pintype "passive"))
      (node (ref "U4") (pin "4") (pinfunction "GND_4") (pintype "passive"))
      (node (ref "U5") (pin "4") (pinfunction "V-_4") (pintype "passive"))
    )
    (net (code "19") (name "Net-(C33-Pad1)") (class "Default")
      (node (ref "C33") (pin "1") (pinfunction "1_1") (pintype "passive"))
      (node (ref "C34") (pin "2") (pinfunction "2_2") (pintype "passive"))
    )
    (net (code "20") (name "Net-(C40-Pad1)") (class "Default")
      (node (ref "C40") (pin "1") (pinfunction "1_1") (pintype "passive"))
      (node (ref "C41") (pin "2") (pinfunction "2_2") (pintype "passive"))
    )
    (net (code "21") (name "Net-(U1-TRIM)") (class "Default")
      (node (ref "C14") (pin "2") (pinfunction "2_2") (pintype "passive"))
      (node (ref "U1") (pin "5") (pinfunction "TRIM_5") (pintype "passive"))
    )
    (net (code "22") (name "Net-(U1-VOUT)") (class "Default")
      (node (ref "C15") (pin "2") (pinfunction "2_2") (pintype "passive"))
      (node (ref "C16") (pin "2") (pinfunction "2_2") (pintype "passive"))
      (node (ref "R2") (pin "1") (pinfunction "1_1") (pintype "passive"))
      (node (ref "U1") (pin "6") (pinfunction "VOUT_6") (pintype "passive"))
    )
    (net (code "23") (name "Net-(U2A-AINN)") (class "Default")
      (node (ref "C38") (pin "1") (pinfunction "1_1") (pintype "passive"))
      (node (ref "C42") (pin "2") (pinfunction "2_2") (pintype "passive"))
      (node (ref "R22") (pin "2") (pinfunction "2_2") (pintype "passive"))
      (node (ref "U2") (pin "4") (pinfunction "AINN_4") (pintype "input"))
    )
    (net (code "24") (name "Net-(U2A-AINP)") (class "Default")
      (node (ref "C37") (pin "2") (pinfunction "2_2") (pintype "passive"))
      (node (ref "C38") (pin "2") (pinfunction "2_2") (pintype "passive"))
      (node (ref "R16") (pin "2") (pinfunction "2_2") (pintype "passive"))
      (node (ref "U2") (pin "5") (pinfunction "AINP_5") (pintype "input"))
    )
    (net (code "25") (name "Net-(U2A-DOUT)") (class "Default")
      (node (ref "R18") (pin "1") (pinfunction "1_1") (pintype "passive"))
      (node (ref "U2") (pin "44") (pinfunction "DOUT_44") (pintype "output"))
    )
    (net (code "26") (name "Net-(U2A-DRDY)") (class "Default")
      (node (ref "R23") (pin "1") (pinfunction "1_1") (pintype "passive"))
      (node (ref "U2") (pin "46") (pinfunction "DRDY_46") (pintype "output"))
    )
    (net (code "27") (name "Net-(U2A-START)") (class "Default")
      (node (ref "R19") (pin "2") (pinfunction "2_2") (pintype "passive"))
      (node (ref "U2") (pin "37") (pinfunction "START_37") (pintype "input"))
    )
    (net (code "28") (name "Net-(U2C-CAP1)") (class "Default")
      (node (ref "C44") (pin "1") (pinfunction "1_1") (pintype "passive"))
      (node (ref "U2") (pin "59") (pinfunction "CAP1_59") (pintype "bidirectional"))
    )
    (net (code "29") (name "Net-(U2C-CAP2)") (class "Default")
      (node (ref "C43") (pin "1") (pinfunction "1_1") (pintype "passive"))
      (node (ref "U2") (pin "62") (pinfunction "CAP2_62") (pintype "bidirectional"))
    )
    (net (code "30") (name "Net-(U2C-CLK)") (class "Default")
      (node (ref "R88") (pin "2") (pinfunction "2_2") (pintype "passive"))
      (node (ref "U2") (pin "55") (pinfunction "CLK_55") (pintype "input"))
    )
    (net (code "31") (name "Net-(U2C-RBIAS)") (class "Default")
      (node (ref "R20") (pin "1") (pinfunction "1_1") (pintype "passive"))
      (node (ref "U2") (pin "8") (pinfunction "RBIAS_8") (pintype "bidirectional"))
    )
    (net (code "32") (name "Net-(U2C-VCM)") (class "Default")
      (node (ref "C39") (pin "2") (pinfunction "2_2") (pintype "passive"))
      (node (ref "U2") (pin "13") (pinfunction "VCM_13") (pintype "bidirectional"))
    )
    (net (code "33") (name "Net-(U3-+IN)") (class "Default")
      (node (ref "C30") (pin "1") (pinfunction "1_1") (pintype "passive"))
      (node (ref "C31") (pin "1") (pinfunction "1_1") (pintype "passive"))
      (node (ref "C32") (pin "2") (pinfunction "2_2") (pintype "passive"))
      (node (ref "R3") (pin "2") (pinfunction "2_2") (pintype "passive"))
      (node (ref "U3") (pin "3") (pinfunction "+IN_3") (pintype "passive"))
    )
    (net (code "34") (name "Net-(U3--IN)") (class "Default")
      (node (ref "C1") (pin "2") (pinfunction "2_2") (pintype "passive"))
      (node (ref "R1") (pin "2") (pinfunction "2_2") (pintype "passive"))
      (node (ref "U3") (pin "2") (pinfunction "-IN_2") (pintype "passive"))
    )
    (net (code "35") (name "Net-(U3-OUT)") (class "Default")
      (node (ref "C1") (pin "1") (pinfunction "1_1") (pintype "passive"))
      (node (ref "R4") (pin "2") (pinfunction "2_2") (pintype "passive"))
      (node (ref "U3") (pin "6") (pinfunction "OUT_6") (pintype "passive"))
    )
    (net (code "36") (name "Net-(U4-TRIM)") (class "Default")
      (node (ref "C28") (pin "1") (pinfunction "1_1") (pintype "passive"))
      (node (ref "U4") (pin "5") (pinfunction "TRIM_5") (pintype "passive"))
    )
    (net (code "37") (name "Net-(U4-VOUT)") (class "Default")
      (node (ref "C29") (pin "1") (pinfunction "1_1") (pintype "passive"))
      (node (ref "R3") (pin "1") (pinfunction "1_1") (pintype "passive"))
      (node (ref "U4") (pin "6") (pinfunction "VOUT_6") (pintype "passive"))
    )
    (net (code "38") (name "Net-(U5A--IN_A)") (class "Default")
      (node (ref "C33") (pin "2") (pinfunction "2_2") (pintype "passive"))
      (node (ref "PD1") (pin "K") (pinfunction "K_K") (pintype "output"))
      (node (ref "R5") (pin "1") (pinfunction "1_1") (pintype "passive"))
      (node (ref "U5") (pin "2") (pinfunction "-IN_A_2") (pintype "passive"))
    )
    (net (code "39") (name "Net-(U5A-OUT_A)") (class "Default")
      (node (ref "C34") (pin "1") (pinfunction "1_1") (pintype "passive"))
      (node (ref "R16") (pin "1") (pinfunction "1_1") (pintype "passive"))
      (node (ref "R5") (pin "2") (pinfunction "2_2") (pintype "passive"))
      (node (ref "U5") (pin "1") (pinfunction "OUT_A_1") (pintype "passive"))
    )
    (net (code "40") (name "Net-(U5B--IN_B)") (class "Default")
      (node (ref "C40") (pin "2") (pinfunction "2_2") (pintype "passive"))
      (node (ref "PD1") (pin "A") (pinfunction "A_A") (pintype "input"))
      (node (ref "R21") (pin "1") (pinfunction "1_1") (pintype "passive"))
      (node (ref "U5") (pin "6") (pinfunction "-IN_B_6") (pintype "passive"))
    )
    (net (code "41") (name "Net-(U5B-OUT_B)") (class "Default")
      (node (ref "C41") (pin "1") (pinfunction "1_1") (pintype "passive"))
      (node (ref "R21") (pin "2") (pinfunction "2_2") (pintype "passive"))
      (node (ref "R22") (pin "1") (pinfunction "1_1") (pintype "passive"))
      (node (ref "U5") (pin "7") (pinfunction "OUT_B_7") (pintype "passive"))
    )
    (net (code "42") (name "Net-(U17-BYPASS)") (class "Default")
      (node (ref "C87") (pin "1") (pinfunction "1_1") (pintype "passive"))
      (node (ref "U17") (pin "4") (pinfunction "BYPASS_4") (pintype "bidirectional"))
    )
    (net (code "43") (name "unconnected-(U1-DNC_1-Pad1)") (class "Default")
      (node (ref "U1") (pin "1") (pinfunction "DNC_1_1") (pintype "passive+no_connect"))
    )
    (net (code "44") (name "unconnected-(U1-DNC_2-Pad8)") (class "Default")
      (node (ref "U1") (pin "8") (pinfunction "DNC_2_8") (pintype "passive+no_connect"))
    )
    (net (code "45") (name "unconnected-(U1-NIC_1-Pad3)") (class "Default")
      (node (ref "U1") (pin "3") (pinfunction "NIC_1_3") (pintype "passive+no_connect"))
    )
    (net (code "46") (name "unconnected-(U1-NIC_2-Pad7)") (class "Default")
      (node (ref "U1") (pin "7") (pinfunction "NIC_2_7") (pintype "passive+no_connect"))
    )
    (net (code "47") (name "unconnected-(U2A-~{DOUT}-Pad43)") (class "Default")
      (node (ref "U2") (pin "43") (pinfunction "~{DOUT}_43") (pintype "output+no_connect"))
    )
    (net (code "48") (name "unconnected-(U2A-~{DRDY}-Pad45)") (class "Default")
      (node (ref "U2") (pin "45") (pinfunction "~{DRDY}_45") (pintype "output+no_connect"))
    )
    (net (code "49") (name "unconnected-(U2C-OTRA-Pad40)") (class "Default")
      (node (ref "U2") (pin "40") (pinfunction "OTRA_40") (pintype "input+no_connect"))
    )
    (net (code "50") (name "unconnected-(U2C-OTRD-Pad39)") (class "Default")
      (node (ref "U2") (pin "39") (pinfunction "OTRD_39") (pintype "input+no_connect"))
    )
    (net (code "51") (name "unconnected-(U2C-~{SCLK}-Pad41)") (class "Default")
      (node (ref "U2") (pin "41") (pinfunction "~{SCLK}_41") (pintype "output+no_connect"))
    )
    (net (code "52") (name "unconnected-(U3-NC_1-Pad1)") (class "Default")
      (node (ref "U3") (pin "1") (pinfunction "NC_1_1") (pintype "passive+no_connect"))
    )
    (net (code "53") (name "unconnected-(U3-NC_2-Pad5)") (class "Default")
      (node (ref "U3") (pin "5") (pinfunction "NC_2_5") (pintype "passive+no_connect"))
    )
  )
)
